# motorcontroller_doppeleinheit.net
KiCad netlist of a schematic drawn in EAGLE
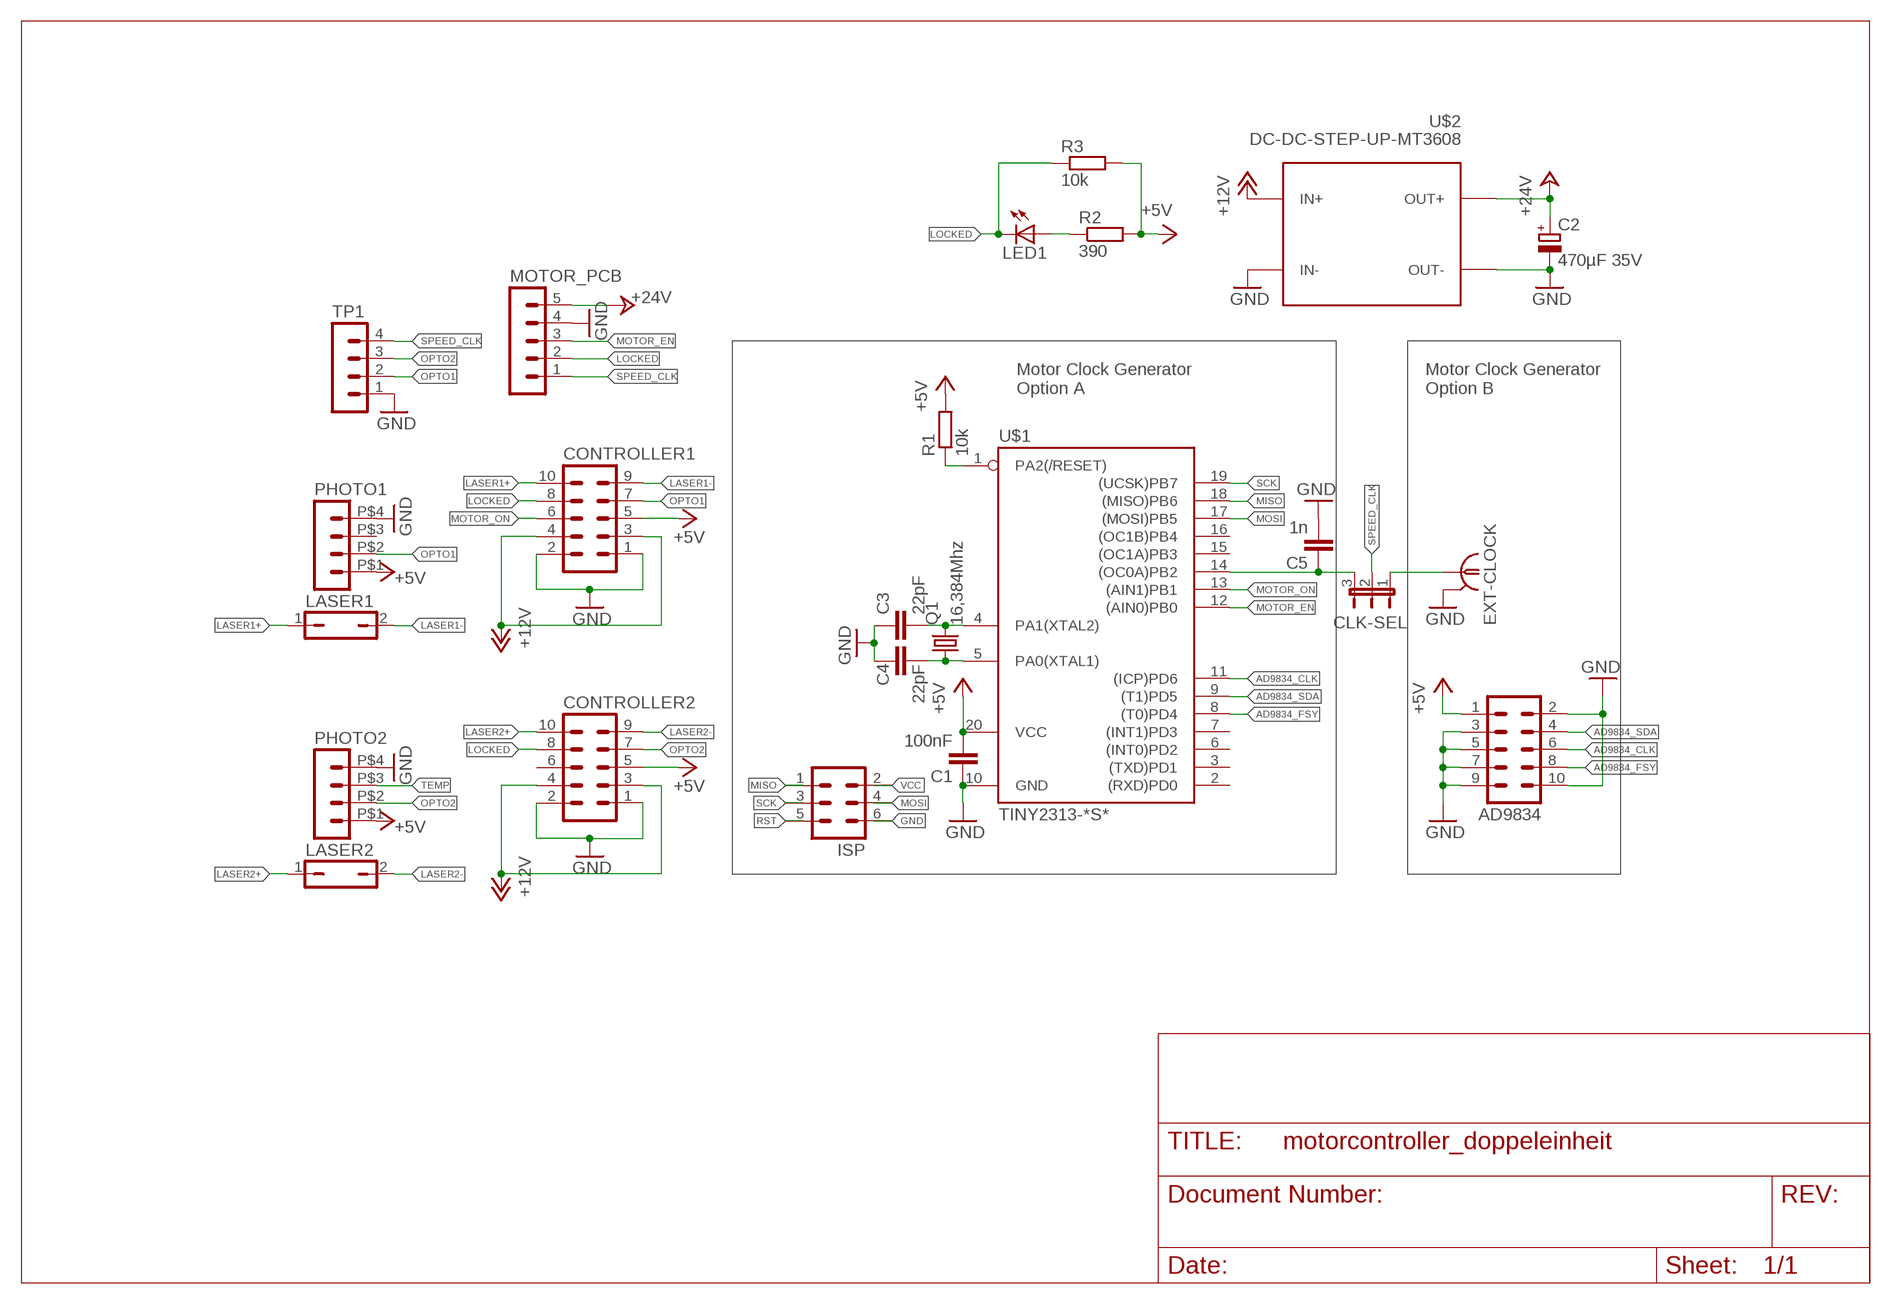
[diagram p0: schematic, sheet 1]

(export (version "E")
  (design (tool "Eeschema 10.0.6"))
  (components
    (comp (ref "AD9834")
      (value "ML10")
      (footprint "eagle-import:ML10")
      (libsource (lib "eagle-import") (part "ML10"))
    )
    (comp (ref "C1")
      (value "100nF")
      (footprint "eagle-import:C1206")
      (libsource (lib "eagle-import") (part "C-EUC1206"))
    )
    (comp (ref "C2")
      (value "470µF 35V")
      (footprint "eagle-import:E5-6")
      (libsource (lib "eagle-import") (part "CPOL-EUE5-6"))
    )
    (comp (ref "C3")
      (value "22pF")
      (footprint "eagle-import:C1206")
      (libsource (lib "eagle-import") (part "C-EUC1206"))
    )
    (comp (ref "C4")
      (value "22pF")
      (footprint "eagle-import:C1206")
      (libsource (lib "eagle-import") (part "C-EUC1206"))
    )
    (comp (ref "C5")
      (value "1n")
      (footprint "eagle-import:C1206")
      (libsource (lib "eagle-import") (part "C-EUC1206"))
    )
    (comp (ref "CLK-SEL")
      (value "JP2E")
      (footprint "eagle-import:JP2")
      (libsource (lib "eagle-import") (part "JP2E"))
    )
    (comp (ref "CONTROLLER1")
      (value "ML10")
      (footprint "eagle-import:ML10")
      (libsource (lib "eagle-import") (part "ML10"))
    )
    (comp (ref "CONTROLLER2")
      (value "ML10")
      (footprint "eagle-import:ML10")
      (libsource (lib "eagle-import") (part "ML10"))
    )
    (comp (ref "EXT-CLOCK")
      (value "LTI-SASF54GT")
      (footprint "eagle-import:LTI-SASF54GT")
      (libsource (lib "eagle-import") (part "LTI-SASF54GT"))
    )
    (comp (ref "ISP")
      (value "ML6L")
      (footprint "eagle-import:ML6L")
      (libsource (lib "eagle-import") (part "ML6L"))
    )
    (comp (ref "LASER1")
      (value "JP1Q")
      (footprint "eagle-import:JP1")
      (libsource (lib "eagle-import") (part "JP1Q"))
    )
    (comp (ref "LASER2")
      (value "JP1Q")
      (footprint "eagle-import:JP1")
      (libsource (lib "eagle-import") (part "JP1Q"))
    )
    (comp (ref "LED1")
      (value "LED3MM")
      (footprint "eagle-import:LED3MM")
      (libsource (lib "eagle-import") (part "LED3MM"))
    )
    (comp (ref "MOTOR_PCB")
      (value "MA05-1")
      (footprint "eagle-import:MA05-1")
      (libsource (lib "eagle-import") (part "MA05-1"))
    )
    (comp (ref "PHOTO1")
      (value "FLAT_P4")
      (footprint "eagle-import:FLAT_4P")
      (libsource (lib "eagle-import") (part "FLAT_P4"))
    )
    (comp (ref "PHOTO2")
      (value "FLAT_P4")
      (footprint "eagle-import:FLAT_4P")
      (libsource (lib "eagle-import") (part "FLAT_P4"))
    )
    (comp (ref "Q1")
      (value "16,384Mhz")
      (footprint "eagle-import:HC49UP")
      (libsource (lib "eagle-import") (part "CRYSTALHC49UP"))
    )
    (comp (ref "R1")
      (value "10k")
      (footprint "eagle-import:R1206")
      (libsource (lib "eagle-import") (part "R-EU_R1206"))
    )
    (comp (ref "R2")
      (value "390")
      (footprint "eagle-import:R1206")
      (libsource (lib "eagle-import") (part "R-EU_R1206"))
    )
    (comp (ref "R3")
      (value "10k")
      (footprint "eagle-import:R1206")
      (libsource (lib "eagle-import") (part "R-EU_R1206"))
    )
    (comp (ref "TP1")
      (value "MA04-1")
      (footprint "eagle-import:MA04-1")
      (libsource (lib "eagle-import") (part "MA04-1"))
    )
    (comp (ref "U$1")
      (value "TINY2313-*S*")
      (footprint "eagle-import:SO20L$")
      (libsource (lib "eagle-import") (part "TINY2313-S"))
    )
    (comp (ref "U$2")
      (value "DC-DC-STEP-UP-MT3608")
      (footprint "eagle-import:DC-DC-STEP-UP-MT3608")
      (libsource (lib "eagle-import") (part "DC-DC-STEP-UP-MT3608"))
    )
  )
  (nets
    (net (code "1") (name "+5V") (class "Default")
      (node (ref "AD9834") (pin "1") (pinfunction "1_1") (pintype "passive"))
      (node (ref "C1") (pin "2") (pinfunction "2_2") (pintype "passive"))
      (node (ref "CONTROLLER1") (pin "5") (pinfunction "5_5") (pintype "passive"))
      (node (ref "CONTROLLER2") (pin "5") (pinfunction "5_5") (pintype "passive"))
      (node (ref "PHOTO1") (pin "P$1") (pinfunction "1_P$1") (pintype "passive"))
      (node (ref "PHOTO2") (pin "P$1") (pinfunction "1_P$1") (pintype "passive"))
      (node (ref "R1") (pin "2") (pinfunction "2_2") (pintype "passive"))
      (node (ref "R2") (pin "2") (pinfunction "2_2") (pintype "passive"))
      (node (ref "R3") (pin "2") (pinfunction "2_2") (pintype "passive"))
      (node (ref "U$1") (pin "20") (pinfunction "VCC_20") (pintype "power_in"))
    )
    (net (code "2") (name "+12V") (class "Default")
      (node (ref "CONTROLLER1") (pin "3") (pinfunction "3_3") (pintype "passive"))
      (node (ref "CONTROLLER1") (pin "4") (pinfunction "4_4") (pintype "passive"))
      (node (ref "CONTROLLER2") (pin "3") (pinfunction "3_3") (pintype "passive"))
      (node (ref "CONTROLLER2") (pin "4") (pinfunction "4_4") (pintype "passive"))
      (node (ref "U$2") (pin "IN+") (pinfunction "IN+_IN+") (pintype "bidirectional"))
    )
    (net (code "3") (name "+24V") (class "Default")
      (node (ref "C2") (pin "+") (pinfunction "+_+") (pintype "passive"))
      (node (ref "MOTOR_PCB") (pin "5") (pinfunction "5_5") (pintype "passive"))
      (node (ref "U$2") (pin "OUT+") (pinfunction "OUT+_OUT+") (pintype "bidirectional"))
    )
    (net (code "4") (name "AD9834_CLK") (class "Default")
      (node (ref "AD9834") (pin "6") (pinfunction "6_6") (pintype "passive"))
      (node (ref "U$1") (pin "11") (pinfunction "(ICP)PD6_11") (pintype "bidirectional"))
    )
    (net (code "5") (name "AD9834_FSY") (class "Default")
      (node (ref "AD9834") (pin "8") (pinfunction "8_8") (pintype "passive"))
      (node (ref "U$1") (pin "8") (pinfunction "(T0)PD4_8") (pintype "bidirectional"))
    )
    (net (code "6") (name "AD9834_SDA") (class "Default")
      (node (ref "AD9834") (pin "4") (pinfunction "4_4") (pintype "passive"))
      (node (ref "U$1") (pin "9") (pinfunction "(T1)PD5_9") (pintype "bidirectional"))
    )
    (net (code "7") (name "GND") (class "Default")
      (node (ref "AD9834") (pin "10") (pinfunction "10_10") (pintype "passive"))
      (node (ref "AD9834") (pin "2") (pinfunction "2_2") (pintype "passive"))
      (node (ref "AD9834") (pin "3") (pinfunction "3_3") (pintype "passive"))
      (node (ref "AD9834") (pin "5") (pinfunction "5_5") (pintype "passive"))
      (node (ref "AD9834") (pin "7") (pinfunction "7_7") (pintype "passive"))
      (node (ref "AD9834") (pin "9") (pinfunction "9_9") (pintype "passive"))
      (node (ref "C1") (pin "1") (pinfunction "1_1") (pintype "passive"))
      (node (ref "C2") (pin "-") (pinfunction "-_-") (pintype "passive"))
      (node (ref "C3") (pin "1") (pinfunction "1_1") (pintype "passive"))
      (node (ref "C4") (pin "1") (pinfunction "1_1") (pintype "passive"))
      (node (ref "C5") (pin "2") (pinfunction "2_2") (pintype "passive"))
      (node (ref "CONTROLLER1") (pin "1") (pinfunction "1_1") (pintype "passive"))
      (node (ref "CONTROLLER1") (pin "2") (pinfunction "2_2") (pintype "passive"))
      (node (ref "CONTROLLER2") (pin "1") (pinfunction "1_1") (pintype "passive"))
      (node (ref "CONTROLLER2") (pin "2") (pinfunction "2_2") (pintype "passive"))
      (node (ref "EXT-CLOCK") (pin "2") (pinfunction "2_2") (pintype "passive"))
      (node (ref "EXT-CLOCK") (pin "3") (pinfunction "2_3") (pintype "passive"))
      (node (ref "EXT-CLOCK") (pin "4") (pinfunction "2_4") (pintype "passive"))
      (node (ref "EXT-CLOCK") (pin "5") (pinfunction "2_5") (pintype "passive"))
      (node (ref "ISP") (pin "6") (pinfunction "6_6") (pintype "passive"))
      (node (ref "MOTOR_PCB") (pin "4") (pinfunction "4_4") (pintype "passive"))
      (node (ref "PHOTO1") (pin "P$4") (pinfunction "4_P$4") (pintype "passive"))
      (node (ref "PHOTO2") (pin "P$4") (pinfunction "4_P$4") (pintype "passive"))
      (node (ref "TP1") (pin "1") (pinfunction "1_1") (pintype "passive"))
      (node (ref "U$1") (pin "10") (pinfunction "GND_10") (pintype "power_in"))
      (node (ref "U$2") (pin "IN-") (pinfunction "IN-_IN-") (pintype "bidirectional"))
      (node (ref "U$2") (pin "OUT-") (pinfunction "OUT-_OUT-") (pintype "bidirectional"))
    )
    (net (code "8") (name "LASER1+") (class "Default")
      (node (ref "CONTROLLER1") (pin "10") (pinfunction "10_10") (pintype "passive"))
      (node (ref "LASER1") (pin "1") (pinfunction "1_1") (pintype "passive"))
    )
    (net (code "9") (name "LASER1-") (class "Default")
      (node (ref "CONTROLLER1") (pin "9") (pinfunction "9_9") (pintype "passive"))
      (node (ref "LASER1") (pin "2") (pinfunction "2_2") (pintype "passive"))
    )
    (net (code "10") (name "LASER2+") (class "Default")
      (node (ref "CONTROLLER2") (pin "10") (pinfunction "10_10") (pintype "passive"))
      (node (ref "LASER2") (pin "1") (pinfunction "1_1") (pintype "passive"))
    )
    (net (code "11") (name "LASER2-") (class "Default")
      (node (ref "CONTROLLER2") (pin "9") (pinfunction "9_9") (pintype "passive"))
      (node (ref "LASER2") (pin "2") (pinfunction "2_2") (pintype "passive"))
    )
    (net (code "12") (name "LOCKED") (class "Default")
      (node (ref "CONTROLLER1") (pin "8") (pinfunction "8_8") (pintype "passive"))
      (node (ref "CONTROLLER2") (pin "8") (pinfunction "8_8") (pintype "passive"))
      (node (ref "LED1") (pin "K") (pinfunction "C_K") (pintype "passive"))
      (node (ref "MOTOR_PCB") (pin "2") (pinfunction "2_2") (pintype "passive"))
      (node (ref "R3") (pin "1") (pinfunction "1_1") (pintype "passive"))
    )
    (net (code "13") (name "MISO") (class "Default")
      (node (ref "ISP") (pin "1") (pinfunction "1_1") (pintype "passive"))
      (node (ref "U$1") (pin "18") (pinfunction "(MISO)PB6_18") (pintype "bidirectional"))
    )
    (net (code "14") (name "MOSI") (class "Default")
      (node (ref "ISP") (pin "4") (pinfunction "4_4") (pintype "passive"))
      (node (ref "U$1") (pin "17") (pinfunction "(MOSI)PB5_17") (pintype "bidirectional"))
    )
    (net (code "15") (name "MOTOR_EN") (class "Default")
      (node (ref "MOTOR_PCB") (pin "3") (pinfunction "3_3") (pintype "passive"))
      (node (ref "U$1") (pin "12") (pinfunction "(AIN0)PB0_12") (pintype "bidirectional"))
    )
    (net (code "16") (name "MOTOR_ON") (class "Default")
      (node (ref "CONTROLLER1") (pin "6") (pinfunction "6_6") (pintype "passive"))
      (node (ref "U$1") (pin "13") (pinfunction "(AIN1)PB1_13") (pintype "bidirectional"))
    )
    (net (code "17") (name "Net-(CLK-SEL-Pad1)") (class "Default")
      (node (ref "CLK-SEL") (pin "1") (pinfunction "1_1") (pintype "passive"))
      (node (ref "EXT-CLOCK") (pin "1") (pinfunction "1_1") (pintype "passive"))
    )
    (net (code "18") (name "Net-(LED1-PadA)") (class "Default")
      (node (ref "LED1") (pin "A") (pinfunction "A_A") (pintype "passive"))
      (node (ref "R2") (pin "1") (pinfunction "1_1") (pintype "passive"))
    )
    (net (code "19") (name "Net-(U$1-(OC0A)PB2)") (class "Default")
      (node (ref "C5") (pin "1") (pinfunction "1_1") (pintype "passive"))
      (node (ref "CLK-SEL") (pin "3") (pinfunction "3_3") (pintype "passive"))
      (node (ref "U$1") (pin "14") (pinfunction "(OC0A)PB2_14") (pintype "bidirectional"))
    )
    (net (code "20") (name "Net-(U$1-PA0(XTAL1))") (class "Default")
      (node (ref "C4") (pin "2") (pinfunction "2_2") (pintype "passive"))
      (node (ref "Q1") (pin "1") (pinfunction "1_1") (pintype "passive"))
      (node (ref "U$1") (pin "5") (pinfunction "PA0(XTAL1)_5") (pintype "bidirectional"))
    )
    (net (code "21") (name "Net-(U$1-PA1(XTAL2))") (class "Default")
      (node (ref "C3") (pin "2") (pinfunction "2_2") (pintype "passive"))
      (node (ref "Q1") (pin "2") (pinfunction "2_2") (pintype "passive"))
      (node (ref "U$1") (pin "4") (pinfunction "PA1(XTAL2)_4") (pintype "bidirectional"))
    )
    (net (code "22") (name "OPTO1") (class "Default")
      (node (ref "CONTROLLER1") (pin "7") (pinfunction "7_7") (pintype "passive"))
      (node (ref "PHOTO1") (pin "P$2") (pinfunction "2_P$2") (pintype "passive"))
      (node (ref "TP1") (pin "2") (pinfunction "2_2") (pintype "passive"))
    )
    (net (code "23") (name "OPTO2") (class "Default")
      (node (ref "CONTROLLER2") (pin "7") (pinfunction "7_7") (pintype "passive"))
      (node (ref "PHOTO2") (pin "P$2") (pinfunction "2_P$2") (pintype "passive"))
      (node (ref "TP1") (pin "3") (pinfunction "3_3") (pintype "passive"))
    )
    (net (code "24") (name "RST") (class "Default")
      (node (ref "ISP") (pin "5") (pinfunction "5_5") (pintype "passive"))
      (node (ref "R1") (pin "1") (pinfunction "1_1") (pintype "passive"))
      (node (ref "U$1") (pin "1") (pinfunction "PA2(/RESET)_1") (pintype "input"))
    )
    (net (code "25") (name "SCK") (class "Default")
      (node (ref "ISP") (pin "3") (pinfunction "3_3") (pintype "passive"))
      (node (ref "U$1") (pin "19") (pinfunction "(UCSK)PB7_19") (pintype "bidirectional"))
    )
    (net (code "26") (name "SPEED_CLK") (class "Default")
      (node (ref "CLK-SEL") (pin "2") (pinfunction "2_2") (pintype "passive"))
      (node (ref "MOTOR_PCB") (pin "1") (pinfunction "1_1") (pintype "passive"))
      (node (ref "TP1") (pin "4") (pinfunction "4_4") (pintype "passive"))
    )
    (net (code "27") (name "TEMP") (class "Default")
      (node (ref "PHOTO2") (pin "P$3") (pinfunction "3_P$3") (pintype "passive"))
    )
    (net (code "28") (name "VCC") (class "Default")
      (node (ref "ISP") (pin "2") (pinfunction "2_2") (pintype "passive"))
    )
    (net (code "29") (name "unconnected-(CONTROLLER2-Pad6)") (class "Default")
      (node (ref "CONTROLLER2") (pin "6") (pinfunction "6_6") (pintype "passive"))
    )
    (net (code "30") (name "unconnected-(PHOTO1-3-PadP$3)") (class "Default")
      (node (ref "PHOTO1") (pin "P$3") (pinfunction "3_P$3") (pintype "passive"))
    )
    (net (code "31") (name "unconnected-(U$1-(INT0)PD2-Pad6)") (class "Default")
      (node (ref "U$1") (pin "6") (pinfunction "(INT0)PD2_6") (pintype "bidirectional"))
    )
    (net (code "32") (name "unconnected-(U$1-(INT1)PD3-Pad7)") (class "Default")
      (node (ref "U$1") (pin "7") (pinfunction "(INT1)PD3_7") (pintype "bidirectional"))
    )
    (net (code "33") (name "unconnected-(U$1-(OC1A)PB3-Pad15)") (class "Default")
      (node (ref "U$1") (pin "15") (pinfunction "(OC1A)PB3_15") (pintype "bidirectional"))
    )
    (net (code "34") (name "unconnected-(U$1-(OC1B)PB4-Pad16)") (class "Default")
      (node (ref "U$1") (pin "16") (pinfunction "(OC1B)PB4_16") (pintype "bidirectional"))
    )
    (net (code "35") (name "unconnected-(U$1-(RXD)PD0-Pad2)") (class "Default")
      (node (ref "U$1") (pin "2") (pinfunction "(RXD)PD0_2") (pintype "bidirectional"))
    )
    (net (code "36") (name "unconnected-(U$1-(TXD)PD1-Pad3)") (class "Default")
      (node (ref "U$1") (pin "3") (pinfunction "(TXD)PD1_3") (pintype "bidirectional"))
    )
  )
)
